# crown-F.net
KiCad netlist of a schematic drawn in EAGLE
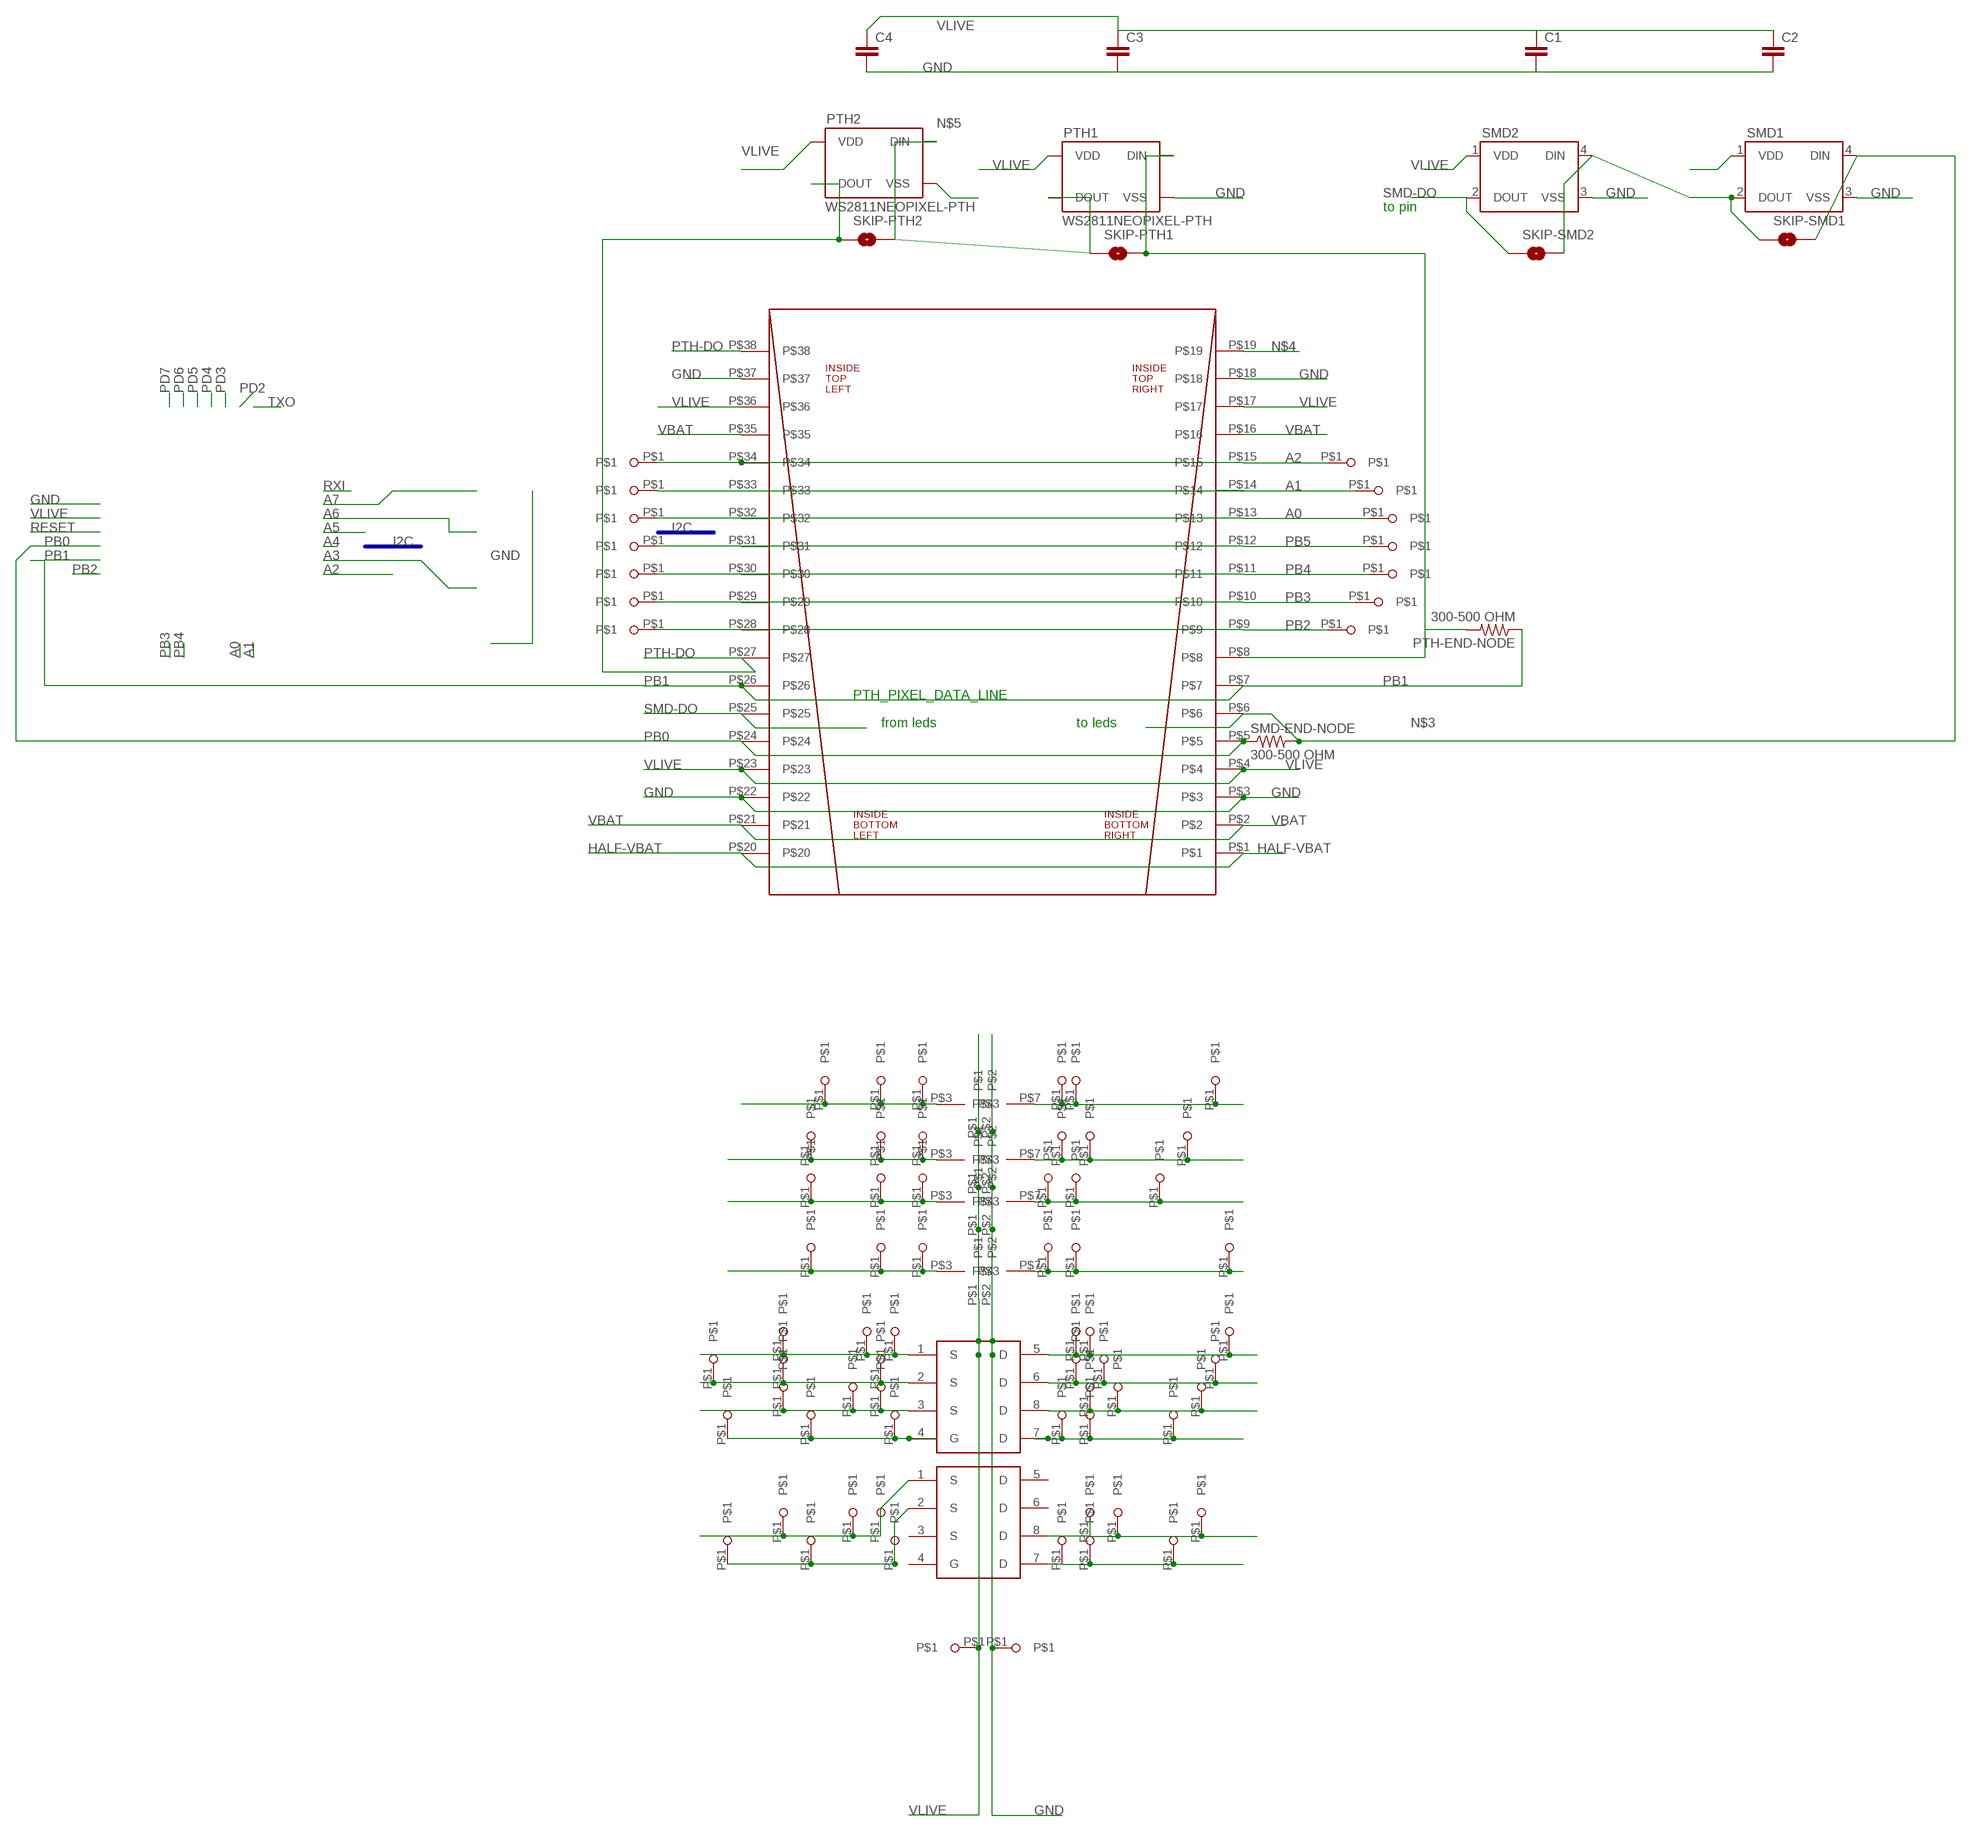
[diagram p0: schematic, sheet 1]

(export (version "E")
  (design (tool "Eeschema 10.0.6"))
  (components
    (comp (ref "C1")
      (value "CAP0805")
      (footprint "eagle-import:0805")
      (libsource (lib "eagle-import") (part "CAP0805"))
    )
    (comp (ref "C2")
      (value "CAP0805")
      (footprint "eagle-import:0805")
      (libsource (lib "eagle-import") (part "CAP0805"))
    )
    (comp (ref "C3")
      (value "CAP0805")
      (footprint "eagle-import:0805")
      (libsource (lib "eagle-import") (part "CAP0805"))
    )
    (comp (ref "C4")
      (value "CAP0805")
      (footprint "eagle-import:0805")
      (libsource (lib "eagle-import") (part "CAP0805"))
    )
    (comp (ref "PTH-END-NODE")
      (value "300-500 OHM")
      (footprint "eagle-import:0805")
      (libsource (lib "eagle-import") (part "RESISTOR0805-RES"))
    )
    (comp (ref "PTH1")
      (value "WS2811NEOPIXEL-PTH")
      (footprint "eagle-import:WS2811-PTH-FLAT")
      (libsource (lib "eagle-import") (part "WS2811NEOPIXEL-PTH"))
    )
    (comp (ref "PTH2")
      (value "WS2811NEOPIXEL-PTH")
      (footprint "eagle-import:WS2811-PTH-FLAT")
      (libsource (lib "eagle-import") (part "WS2811NEOPIXEL-PTH"))
    )
    (comp (ref "SKIP-PTH1")
      (value "SOLDERJUMPERNC2")
      (footprint "eagle-import:SJ_2S-NOTRACE")
      (libsource (lib "eagle-import") (part "SOLDERJUMPERNC2"))
    )
    (comp (ref "SKIP-PTH2")
      (value "SOLDERJUMPERNC2")
      (footprint "eagle-import:SJ_2S-NOTRACE")
      (libsource (lib "eagle-import") (part "SOLDERJUMPERNC2"))
    )
    (comp (ref "SKIP-SMD1")
      (value "SOLDERJUMPERNC2")
      (footprint "eagle-import:SJ_2S-NOTRACE")
      (libsource (lib "eagle-import") (part "SOLDERJUMPERNC2"))
    )
    (comp (ref "SKIP-SMD2")
      (value "SOLDERJUMPERNC2")
      (footprint "eagle-import:SJ_2S-NOTRACE")
      (libsource (lib "eagle-import") (part "SOLDERJUMPERNC2"))
    )
    (comp (ref "SMD-END-NODE")
      (value "300-500 OHM")
      (footprint "eagle-import:0805")
      (libsource (lib "eagle-import") (part "RESISTOR0805-RES"))
    )
    (comp (ref "SMD1")
      (value "WS2812B")
      (footprint "eagle-import:WS2812B")
      (libsource (lib "eagle-import") (part "WS2812B"))
    )
    (comp (ref "SMD2")
      (value "WS2812B")
      (footprint "eagle-import:WS2812B")
      (libsource (lib "eagle-import") (part "WS2812B"))
    )
    (comp (ref "U$1")
      (value "SMD_PAD")
      (footprint "eagle-import:SMD_BREADBOARD_PAD")
      (libsource (lib "eagle-import") (part "SMD_PAD"))
    )
    (comp (ref "U$2")
      (value "CROWNSTANDARD")
      (footprint "eagle-import:CROWN")
      (libsource (lib "eagle-import") (part "CROWNSTANDARD"))
    )
    (comp (ref "U$3")
      (value "SMD_PAD")
      (footprint "eagle-import:SMD_BREADBOARD_PAD")
      (libsource (lib "eagle-import") (part "SMD_PAD"))
    )
    (comp (ref "U$4")
      (value "SMD_BREADBOARD")
      (footprint "eagle-import:SMD_BREADBOARD_4X")
      (libsource (lib "eagle-import") (part "SMD_BREADBOARD"))
    )
    (comp (ref "U$5")
      (value "SMD_BREADBOARD")
      (footprint "eagle-import:SMD_BREADBOARD_4X")
      (libsource (lib "eagle-import") (part "SMD_BREADBOARD"))
    )
    (comp (ref "U$6")
      (value "SMD_BREADBOARD")
      (footprint "eagle-import:SMD_BREADBOARD_4X")
      (libsource (lib "eagle-import") (part "SMD_BREADBOARD"))
    )
    (comp (ref "U$7")
      (value "SMD_BREADBOARD")
      (footprint "eagle-import:SMD_BREADBOARD_4X")
      (libsource (lib "eagle-import") (part "SMD_BREADBOARD"))
    )
    (comp (ref "U$8")
      (value "SMD_PAD")
      (footprint "eagle-import:SMD_BREADBOARD_PAD")
      (libsource (lib "eagle-import") (part "SMD_PAD"))
    )
    (comp (ref "U$9")
      (value "SMD_PAD")
      (footprint "eagle-import:SMD_BREADBOARD_PAD")
      (libsource (lib "eagle-import") (part "SMD_PAD"))
    )
    (comp (ref "U$10")
      (value "SMD_PAD")
      (footprint "eagle-import:SMD_BREADBOARD_PAD")
      (libsource (lib "eagle-import") (part "SMD_PAD"))
    )
    (comp (ref "U$11")
      (value "SMD_PAD")
      (footprint "eagle-import:SMD_BREADBOARD_PAD")
      (libsource (lib "eagle-import") (part "SMD_PAD"))
    )
    (comp (ref "U$12")
      (value "SMD_PAD")
      (footprint "eagle-import:SMD_BREADBOARD_PAD")
      (libsource (lib "eagle-import") (part "SMD_PAD"))
    )
    (comp (ref "U$13")
      (value "SMD_PAD")
      (footprint "eagle-import:SMD_BREADBOARD_PAD")
      (libsource (lib "eagle-import") (part "SMD_PAD"))
    )
    (comp (ref "U$14")
      (value "SMD_PAD")
      (footprint "eagle-import:SMD_BREADBOARD_PAD")
      (libsource (lib "eagle-import") (part "SMD_PAD"))
    )
    (comp (ref "U$15")
      (value "SMD_PAD")
      (footprint "eagle-import:SMD_BREADBOARD_PAD")
      (libsource (lib "eagle-import") (part "SMD_PAD"))
    )
    (comp (ref "U$16")
      (value "SMD_PAD")
      (footprint "eagle-import:SMD_BREADBOARD_PAD")
      (libsource (lib "eagle-import") (part "SMD_PAD"))
    )
    (comp (ref "U$17")
      (value "SMD_PAD")
      (footprint "eagle-import:SMD_BREADBOARD_PAD")
      (libsource (lib "eagle-import") (part "SMD_PAD"))
    )
    (comp (ref "U$18")
      (value "SMD_PAD")
      (footprint "eagle-import:SMD_BREADBOARD_PAD")
      (libsource (lib "eagle-import") (part "SMD_PAD"))
    )
    (comp (ref "U$19")
      (value "SMD_PAD")
      (footprint "eagle-import:SMD_BREADBOARD_PAD")
      (libsource (lib "eagle-import") (part "SMD_PAD"))
    )
    (comp (ref "U$20")
      (value "SMD_PAD")
      (footprint "eagle-import:SMD_BREADBOARD_PAD")
      (libsource (lib "eagle-import") (part "SMD_PAD"))
    )
    (comp (ref "U$21")
      (value "SMD_PAD")
      (footprint "eagle-import:SMD_BREADBOARD_PAD")
      (libsource (lib "eagle-import") (part "SMD_PAD"))
    )
    (comp (ref "U$22")
      (value "SMD_PAD")
      (footprint "eagle-import:SMD_BREADBOARD_PAD")
      (libsource (lib "eagle-import") (part "SMD_PAD"))
    )
    (comp (ref "U$23")
      (value "SMD_PAD")
      (footprint "eagle-import:SMD_BREADBOARD_PAD")
      (libsource (lib "eagle-import") (part "SMD_PAD"))
    )
    (comp (ref "U$24")
      (value "SMD_PAD")
      (footprint "eagle-import:SMD_BREADBOARD_PAD")
      (libsource (lib "eagle-import") (part "SMD_PAD"))
    )
    (comp (ref "U$25")
      (value "SMD_PAD")
      (footprint "eagle-import:SMD_BREADBOARD_PAD")
      (libsource (lib "eagle-import") (part "SMD_PAD"))
    )
    (comp (ref "U$26")
      (value "SMD_PAD")
      (footprint "eagle-import:SMD_BREADBOARD_PAD")
      (libsource (lib "eagle-import") (part "SMD_PAD"))
    )
    (comp (ref "U$27")
      (value "SMD_PAD")
      (footprint "eagle-import:SMD_BREADBOARD_PAD")
      (libsource (lib "eagle-import") (part "SMD_PAD"))
    )
    (comp (ref "U$28")
      (value "SMD_PAD")
      (footprint "eagle-import:SMD_BREADBOARD_PAD")
      (libsource (lib "eagle-import") (part "SMD_PAD"))
    )
    (comp (ref "U$29")
      (value "SMD_PAD")
      (footprint "eagle-import:SMD_BREADBOARD_PAD")
      (libsource (lib "eagle-import") (part "SMD_PAD"))
    )
    (comp (ref "U$30")
      (value "SMD_PAD")
      (footprint "eagle-import:SMD_BREADBOARD_PAD")
      (libsource (lib "eagle-import") (part "SMD_PAD"))
    )
    (comp (ref "U$31")
      (value "SMD_PAD")
      (footprint "eagle-import:SMD_BREADBOARD_PAD")
      (libsource (lib "eagle-import") (part "SMD_PAD"))
    )
    (comp (ref "U$32")
      (value "SMD_PAD")
      (footprint "eagle-import:SMD_BREADBOARD_PAD")
      (libsource (lib "eagle-import") (part "SMD_PAD"))
    )
    (comp (ref "U$33")
      (value "SMD_PAD")
      (footprint "eagle-import:SMD_BREADBOARD_PAD")
      (libsource (lib "eagle-import") (part "SMD_PAD"))
    )
    (comp (ref "U$34")
      (value "SMD_PAD")
      (footprint "eagle-import:SMD_BREADBOARD_PAD")
      (libsource (lib "eagle-import") (part "SMD_PAD"))
    )
    (comp (ref "U$35")
      (value "SMD_PAD")
      (footprint "eagle-import:SMD_BREADBOARD_PAD")
      (libsource (lib "eagle-import") (part "SMD_PAD"))
    )
    (comp (ref "U$36")
      (value "SMD_PAD")
      (footprint "eagle-import:SMD_BREADBOARD_PAD")
      (libsource (lib "eagle-import") (part "SMD_PAD"))
    )
    (comp (ref "U$37")
      (value "SMD_PAD")
      (footprint "eagle-import:SMD_BREADBOARD_PAD")
      (libsource (lib "eagle-import") (part "SMD_PAD"))
    )
    (comp (ref "U$38")
      (value "SMD_PAD")
      (footprint "eagle-import:SMD_BREADBOARD_PAD")
      (libsource (lib "eagle-import") (part "SMD_PAD"))
    )
    (comp (ref "U$39")
      (value "SMD_PAD")
      (footprint "eagle-import:SMD_BREADBOARD_PAD")
      (libsource (lib "eagle-import") (part "SMD_PAD"))
    )
    (comp (ref "U$40")
      (value "SMD_PAD")
      (footprint "eagle-import:SMD_BREADBOARD_PAD")
      (libsource (lib "eagle-import") (part "SMD_PAD"))
    )
    (comp (ref "U$41")
      (value "SMD_PAD")
      (footprint "eagle-import:SMD_BREADBOARD_PAD")
      (libsource (lib "eagle-import") (part "SMD_PAD"))
    )
    (comp (ref "U$42")
      (value "SMD_PAD")
      (footprint "eagle-import:SMD_BREADBOARD_PAD")
      (libsource (lib "eagle-import") (part "SMD_PAD"))
    )
    (comp (ref "U$43")
      (value "SMD_PAD")
      (footprint "eagle-import:SMD_BREADBOARD_PAD")
      (libsource (lib "eagle-import") (part "SMD_PAD"))
    )
    (comp (ref "U$44")
      (value "SMD_PAD")
      (footprint "eagle-import:SMD_BREADBOARD_PAD")
      (libsource (lib "eagle-import") (part "SMD_PAD"))
    )
    (comp (ref "U$45")
      (value "SMD_PAD")
      (footprint "eagle-import:SMD_BREADBOARD_PAD")
      (libsource (lib "eagle-import") (part "SMD_PAD"))
    )
    (comp (ref "U$46")
      (value "SMD_PAD")
      (footprint "eagle-import:SMD_BREADBOARD_PAD")
      (libsource (lib "eagle-import") (part "SMD_PAD"))
    )
    (comp (ref "U$47")
      (value "SMD_PAD")
      (footprint "eagle-import:SMD_BREADBOARD_PAD")
      (libsource (lib "eagle-import") (part "SMD_PAD"))
    )
    (comp (ref "U$48")
      (value "SMD_PAD")
      (footprint "eagle-import:SMD_BREADBOARD_PAD")
      (libsource (lib "eagle-import") (part "SMD_PAD"))
    )
    (comp (ref "U$49")
      (value "SMD_PAD")
      (footprint "eagle-import:SMD_BREADBOARD_PAD")
      (libsource (lib "eagle-import") (part "SMD_PAD"))
    )
    (comp (ref "U$50")
      (value "SMD_PAD")
      (footprint "eagle-import:SMD_BREADBOARD_PAD")
      (libsource (lib "eagle-import") (part "SMD_PAD"))
    )
    (comp (ref "U$51")
      (value "SMD_PAD")
      (footprint "eagle-import:SMD_BREADBOARD_PAD")
      (libsource (lib "eagle-import") (part "SMD_PAD"))
    )
    (comp (ref "U$52")
      (value "SMD_PAD")
      (footprint "eagle-import:SMD_BREADBOARD_PAD")
      (libsource (lib "eagle-import") (part "SMD_PAD"))
    )
    (comp (ref "U$53")
      (value "SMD_PAD")
      (footprint "eagle-import:SMD_BREADBOARD_PAD")
      (libsource (lib "eagle-import") (part "SMD_PAD"))
    )
    (comp (ref "U$54")
      (value "SMD_PAD")
      (footprint "eagle-import:SMD_BREADBOARD_PAD")
      (libsource (lib "eagle-import") (part "SMD_PAD"))
    )
    (comp (ref "U$55")
      (value "SMD_PAD")
      (footprint "eagle-import:SMD_BREADBOARD_PAD")
      (libsource (lib "eagle-import") (part "SMD_PAD"))
    )
    (comp (ref "U$56")
      (value "SMD_PAD")
      (footprint "eagle-import:SMD_BREADBOARD_PAD")
      (libsource (lib "eagle-import") (part "SMD_PAD"))
    )
    (comp (ref "U$57")
      (value "SMD_PAD")
      (footprint "eagle-import:SMD_BREADBOARD_PAD")
      (libsource (lib "eagle-import") (part "SMD_PAD"))
    )
    (comp (ref "U$58")
      (value "SMD_PAD")
      (footprint "eagle-import:SMD_BREADBOARD_PAD")
      (libsource (lib "eagle-import") (part "SMD_PAD"))
    )
    (comp (ref "U$59")
      (value "SMD_PAD")
      (footprint "eagle-import:SMD_BREADBOARD_PAD")
      (libsource (lib "eagle-import") (part "SMD_PAD"))
    )
    (comp (ref "U$60")
      (value "SMD_PAD")
      (footprint "eagle-import:SMD_BREADBOARD_PAD")
      (libsource (lib "eagle-import") (part "SMD_PAD"))
    )
    (comp (ref "U$61")
      (value "SMD_PAD")
      (footprint "eagle-import:SMD_BREADBOARD_PAD")
      (libsource (lib "eagle-import") (part "SMD_PAD"))
    )
    (comp (ref "U$62")
      (value "SMD_PAD")
      (footprint "eagle-import:SMD_BREADBOARD_PAD")
      (libsource (lib "eagle-import") (part "SMD_PAD"))
    )
    (comp (ref "U$63")
      (value "SMD_PAD")
      (footprint "eagle-import:SMD_BREADBOARD_PAD")
      (libsource (lib "eagle-import") (part "SMD_PAD"))
    )
    (comp (ref "U$64")
      (value "SMD_PAD")
      (footprint "eagle-import:SMD_BREADBOARD_PAD")
      (libsource (lib "eagle-import") (part "SMD_PAD"))
    )
    (comp (ref "U$65")
      (value "SMD_PAD")
      (footprint "eagle-import:SMD_BREADBOARD_PAD")
      (libsource (lib "eagle-import") (part "SMD_PAD"))
    )
    (comp (ref "U$66")
      (value "SMD_PAD")
      (footprint "eagle-import:SMD_BREADBOARD_PAD")
      (libsource (lib "eagle-import") (part "SMD_PAD"))
    )
    (comp (ref "U$67")
      (value "SMD_PAD")
      (footprint "eagle-import:SMD_BREADBOARD_PAD")
      (libsource (lib "eagle-import") (part "SMD_PAD"))
    )
    (comp (ref "U$68")
      (value "SMD_PAD")
      (footprint "eagle-import:SMD_BREADBOARD_PAD")
      (libsource (lib "eagle-import") (part "SMD_PAD"))
    )
    (comp (ref "U$69")
      (value "SMD_PAD")
      (footprint "eagle-import:SMD_BREADBOARD_PAD")
      (libsource (lib "eagle-import") (part "SMD_PAD"))
    )
    (comp (ref "U$70")
      (value "SMD_PAD")
      (footprint "eagle-import:SMD_BREADBOARD_PAD")
      (libsource (lib "eagle-import") (part "SMD_PAD"))
    )
    (comp (ref "U$71")
      (value "SMD_PAD")
      (footprint "eagle-import:SMD_BREADBOARD_PAD")
      (libsource (lib "eagle-import") (part "SMD_PAD"))
    )
    (comp (ref "U$72")
      (value "NDS8434")
      (footprint "eagle-import:SO08")
      (libsource (lib "eagle-import") (part "NDS8434"))
    )
    (comp (ref "U$73")
      (value "SMD_PAD")
      (footprint "eagle-import:SMD_BREADBOARD_PAD")
      (libsource (lib "eagle-import") (part "SMD_PAD"))
    )
    (comp (ref "U$74")
      (value "SMD_PAD")
      (footprint "eagle-import:SMD_BREADBOARD_PAD")
      (libsource (lib "eagle-import") (part "SMD_PAD"))
    )
    (comp (ref "U$75")
      (value "SMD_PAD")
      (footprint "eagle-import:SMD_BREADBOARD_PAD")
      (libsource (lib "eagle-import") (part "SMD_PAD"))
    )
    (comp (ref "U$76")
      (value "SMD_PAD")
      (footprint "eagle-import:SMD_BREADBOARD_PAD")
      (libsource (lib "eagle-import") (part "SMD_PAD"))
    )
    (comp (ref "U$77")
      (value "SMD_PAD")
      (footprint "eagle-import:SMD_BREADBOARD_PAD")
      (libsource (lib "eagle-import") (part "SMD_PAD"))
    )
    (comp (ref "U$78")
      (value "SMD_PAD")
      (footprint "eagle-import:SMD_BREADBOARD_PAD")
      (libsource (lib "eagle-import") (part "SMD_PAD"))
    )
    (comp (ref "U$79")
      (value "SMD_PAD")
      (footprint "eagle-import:SMD_BREADBOARD_PAD")
      (libsource (lib "eagle-import") (part "SMD_PAD"))
    )
    (comp (ref "U$80")
      (value "SMD_PAD")
      (footprint "eagle-import:SMD_BREADBOARD_PAD")
      (libsource (lib "eagle-import") (part "SMD_PAD"))
    )
    (comp (ref "U$81")
      (value "NDS8434")
      (footprint "eagle-import:SO08")
      (libsource (lib "eagle-import") (part "NDS8434"))
    )
    (comp (ref "U$82")
      (value "SMD_PAD")
      (footprint "eagle-import:SMD_BREADBOARD_PAD")
      (libsource (lib "eagle-import") (part "SMD_PAD"))
    )
    (comp (ref "U$83")
      (value "SMD_PAD")
      (footprint "eagle-import:SMD_BREADBOARD_PAD")
      (libsource (lib "eagle-import") (part "SMD_PAD"))
    )
  )
  (nets
    (net (code "2") (name "/A0") (class "Default")
      (node (ref "U$2") (pin "P$13") (pinfunction "P$13_P$13") (pintype "bidirectional"))
      (node (ref "U$2") (pin "P$32") (pinfunction "P$32_P$32") (pintype "bidirectional"))
      (node (ref "U$44") (pin "P$1") (pinfunction "P$1_P$1") (pintype "bidirectional"))
      (node (ref "U$55") (pin "P$1") (pinfunction "P$1_P$1") (pintype "bidirectional"))
    )
    (net (code "3") (name "/A1") (class "Default")
      (node (ref "U$2") (pin "P$14") (pinfunction "P$14_P$14") (pintype "bidirectional"))
      (node (ref "U$2") (pin "P$33") (pinfunction "P$33_P$33") (pintype "bidirectional"))
      (node (ref "U$43") (pin "P$1") (pinfunction "P$1_P$1") (pintype "bidirectional"))
      (node (ref "U$56") (pin "P$1") (pinfunction "P$1_P$1") (pintype "bidirectional"))
    )
    (net (code "4") (name "/A2") (class "Default")
      (node (ref "U$2") (pin "P$15") (pinfunction "P$15_P$15") (pintype "bidirectional"))
      (node (ref "U$2") (pin "P$34") (pinfunction "P$34_P$34") (pintype "bidirectional"))
      (node (ref "U$42") (pin "P$1") (pinfunction "P$1_P$1") (pintype "bidirectional"))
      (node (ref "U$58") (pin "P$1") (pinfunction "P$1_P$1") (pintype "bidirectional"))
    )
    (net (code "10") (name "/GND") (class "Default")
      (node (ref "C1") (pin "2") (pinfunction "2_2") (pintype "passive"))
      (node (ref "C2") (pin "2") (pinfunction "2_2") (pintype "passive"))
      (node (ref "C3") (pin "2") (pinfunction "2_2") (pintype "passive"))
      (node (ref "C4") (pin "2") (pinfunction "2_2") (pintype "passive"))
      (node (ref "PTH1") (pin "P$2") (pinfunction "VSS_P$2") (pintype "power_in"))
      (node (ref "PTH1") (pin "P$6") (pinfunction "VSS_P$6") (pintype "power_in"))
      (node (ref "PTH2") (pin "P$2") (pinfunction "VSS_P$2") (pintype "power_in"))
      (node (ref "PTH2") (pin "P$6") (pinfunction "VSS_P$6") (pintype "power_in"))
      (node (ref "SMD1") (pin "3") (pinfunction "VSS_3") (pintype "power_in"))
      (node (ref "SMD2") (pin "3") (pinfunction "VSS_3") (pintype "power_in"))
      (node (ref "U$2") (pin "P$18") (pinfunction "P$18_P$18") (pintype "bidirectional"))
      (node (ref "U$2") (pin "P$22") (pinfunction "P$22_P$22") (pintype "bidirectional"))
      (node (ref "U$2") (pin "P$3") (pinfunction "P$3_P$3") (pintype "bidirectional"))
      (node (ref "U$2") (pin "P$37") (pinfunction "P$37_P$37") (pintype "bidirectional"))
      (node (ref "U$4") (pin "P$2") (pinfunction "P$2_P$2") (pintype "bidirectional"))
      (node (ref "U$5") (pin "P$2") (pinfunction "P$2_P$2") (pintype "bidirectional"))
      (node (ref "U$6") (pin "P$2") (pinfunction "P$2_P$2") (pintype "bidirectional"))
      (node (ref "U$7") (pin "P$2") (pinfunction "P$2_P$2") (pintype "bidirectional"))
      (node (ref "U$83") (pin "P$1") (pinfunction "P$1_P$1") (pintype "bidirectional"))
    )
    (net (code "11") (name "/HALF-VBAT") (class "Default")
      (node (ref "U$2") (pin "P$1") (pinfunction "P$1_P$1") (pintype "bidirectional"))
      (node (ref "U$2") (pin "P$20") (pinfunction "P$20_P$20") (pintype "bidirectional"))
    )
    (net (code "12") (name "/N$3") (class "Default")
      (node (ref "SKIP-SMD1") (pin "2") (pinfunction "2_2") (pintype "passive"))
      (node (ref "SMD-END-NODE") (pin "2") (pinfunction "2_2") (pintype "passive"))
      (node (ref "SMD1") (pin "4") (pinfunction "DIN_4") (pintype "input"))
      (node (ref "U$2") (pin "P$6") (pinfunction "P$6_P$6") (pintype "bidirectional"))
    )
    (net (code "13") (name "/N$4") (class "Default")
      (node (ref "PTH-END-NODE") (pin "2") (pinfunction "2_2") (pintype "passive"))
      (node (ref "PTH1") (pin "P$4") (pinfunction "DIN_P$4") (pintype "input"))
      (node (ref "PTH1") (pin "P$8") (pinfunction "DIN_P$8") (pintype "input"))
      (node (ref "SKIP-PTH1") (pin "2") (pinfunction "2_2") (pintype "passive"))
      (node (ref "U$2") (pin "P$19") (pinfunction "P$19_P$19") (pintype "bidirectional"))
      (node (ref "U$2") (pin "P$8") (pinfunction "P$8_P$8") (pintype "bidirectional"))
    )
    (net (code "14") (name "/N$5") (class "Default")
      (node (ref "PTH1") (pin "P$1") (pinfunction "DOUT_P$1") (pintype "output"))
      (node (ref "PTH1") (pin "P$5") (pinfunction "DOUT_P$5") (pintype "output"))
      (node (ref "PTH2") (pin "P$4") (pinfunction "DIN_P$4") (pintype "input"))
      (node (ref "PTH2") (pin "P$8") (pinfunction "DIN_P$8") (pintype "input"))
      (node (ref "SKIP-PTH1") (pin "1") (pinfunction "1_1") (pintype "passive"))
      (node (ref "SKIP-PTH2") (pin "2") (pinfunction "2_2") (pintype "passive"))
    )
    (net (code "15") (name "/PB0") (class "Default")
      (node (ref "SMD-END-NODE") (pin "1") (pinfunction "1_1") (pintype "passive"))
      (node (ref "U$2") (pin "P$24") (pinfunction "P$24_P$24") (pintype "bidirectional"))
      (node (ref "U$2") (pin "P$5") (pinfunction "P$5_P$5") (pintype "bidirectional"))
    )
    (net (code "16") (name "/PB1") (class "Default")
      (node (ref "PTH-END-NODE") (pin "1") (pinfunction "1_1") (pintype "passive"))
      (node (ref "U$2") (pin "P$26") (pinfunction "P$26_P$26") (pintype "bidirectional"))
      (node (ref "U$2") (pin "P$7") (pinfunction "P$7_P$7") (pintype "bidirectional"))
    )
    (net (code "17") (name "/PB2") (class "Default")
      (node (ref "U$2") (pin "P$28") (pinfunction "P$28_P$28") (pintype "bidirectional"))
      (node (ref "U$2") (pin "P$9") (pinfunction "P$9_P$9") (pintype "bidirectional"))
      (node (ref "U$48") (pin "P$1") (pinfunction "P$1_P$1") (pintype "bidirectional"))
      (node (ref "U$51") (pin "P$1") (pinfunction "P$1_P$1") (pintype "bidirectional"))
    )
    (net (code "18") (name "/PB3") (class "Default")
      (node (ref "U$2") (pin "P$10") (pinfunction "P$10_P$10") (pintype "bidirectional"))
      (node (ref "U$2") (pin "P$29") (pinfunction "P$29_P$29") (pintype "bidirectional"))
      (node (ref "U$47") (pin "P$1") (pinfunction "P$1_P$1") (pintype "bidirectional"))
      (node (ref "U$52") (pin "P$1") (pinfunction "P$1_P$1") (pintype "bidirectional"))
    )
    (net (code "19") (name "/PB4") (class "Default")
      (node (ref "U$2") (pin "P$11") (pinfunction "P$11_P$11") (pintype "bidirectional"))
      (node (ref "U$2") (pin "P$30") (pinfunction "P$30_P$30") (pintype "bidirectional"))
      (node (ref "U$46") (pin "P$1") (pinfunction "P$1_P$1") (pintype "bidirectional"))
      (node (ref "U$53") (pin "P$1") (pinfunction "P$1_P$1") (pintype "bidirectional"))
    )
    (net (code "20") (name "/PB5") (class "Default")
      (node (ref "U$2") (pin "P$12") (pinfunction "P$12_P$12") (pintype "bidirectional"))
      (node (ref "U$2") (pin "P$31") (pinfunction "P$31_P$31") (pintype "bidirectional"))
      (node (ref "U$45") (pin "P$1") (pinfunction "P$1_P$1") (pintype "bidirectional"))
      (node (ref "U$54") (pin "P$1") (pinfunction "P$1_P$1") (pintype "bidirectional"))
    )
    (net (code "27") (name "/PTH-DO") (class "Default")
      (node (ref "PTH2") (pin "P$1") (pinfunction "DOUT_P$1") (pintype "output"))
      (node (ref "PTH2") (pin "P$5") (pinfunction "DOUT_P$5") (pintype "output"))
      (node (ref "SKIP-PTH2") (pin "1") (pinfunction "1_1") (pintype "passive"))
      (node (ref "U$2") (pin "P$27") (pinfunction "P$27_P$27") (pintype "bidirectional"))
      (node (ref "U$2") (pin "P$38") (pinfunction "P$38_P$38") (pintype "bidirectional"))
    )
    (net (code "30") (name "/SMD-DO") (class "Default")
      (node (ref "SKIP-SMD2") (pin "1") (pinfunction "1_1") (pintype "passive"))
      (node (ref "SMD2") (pin "2") (pinfunction "DOUT_2") (pintype "output"))
      (node (ref "U$2") (pin "P$25") (pinfunction "P$25_P$25") (pintype "bidirectional"))
    )
    (net (code "32") (name "/VBAT") (class "Default")
      (node (ref "U$2") (pin "P$16") (pinfunction "P$16_P$16") (pintype "bidirectional"))
      (node (ref "U$2") (pin "P$2") (pinfunction "P$2_P$2") (pintype "bidirectional"))
      (node (ref "U$2") (pin "P$21") (pinfunction "P$21_P$21") (pintype "bidirectional"))
      (node (ref "U$2") (pin "P$35") (pinfunction "P$35_P$35") (pintype "bidirectional"))
    )
    (net (code "33") (name "/VLIVE") (class "Default")
      (node (ref "C1") (pin "1") (pinfunction "1_1") (pintype "passive"))
      (node (ref "C2") (pin "1") (pinfunction "1_1") (pintype "passive"))
      (node (ref "C3") (pin "1") (pinfunction "1_1") (pintype "passive"))
      (node (ref "C4") (pin "1") (pinfunction "1_1") (pintype "passive"))
      (node (ref "PTH1") (pin "P$3") (pinfunction "VDD_P$3") (pintype "power_in"))
      (node (ref "PTH1") (pin "P$7") (pinfunction "VDD_P$7") (pintype "power_in"))
      (node (ref "PTH2") (pin "P$3") (pinfunction "VDD_P$3") (pintype "power_in"))
      (node (ref "PTH2") (pin "P$7") (pinfunction "VDD_P$7") (pintype "power_in"))
      (node (ref "SMD1") (pin "1") (pinfunction "VDD_1") (pintype "power_in"))
      (node (ref "SMD2") (pin "1") (pinfunction "VDD_1") (pintype "power_in"))
      (node (ref "U$2") (pin "P$17") (pinfunction "P$17_P$17") (pintype "bidirectional"))
      (node (ref "U$2") (pin "P$23") (pinfunction "P$23_P$23") (pintype "bidirectional"))
      (node (ref "U$2") (pin "P$36") (pinfunction "P$36_P$36") (pintype "bidirectional"))
      (node (ref "U$2") (pin "P$4") (pinfunction "P$4_P$4") (pintype "bidirectional"))
      (node (ref "U$4") (pin "P$1") (pinfunction "P$1_P$1") (pintype "bidirectional"))
      (node (ref "U$5") (pin "P$1") (pinfunction "P$1_P$1") (pintype "bidirectional"))
      (node (ref "U$6") (pin "P$1") (pinfunction "P$1_P$1") (pintype "bidirectional"))
      (node (ref "U$7") (pin "P$1") (pinfunction "P$1_P$1") (pintype "bidirectional"))
      (node (ref "U$82") (pin "P$1") (pinfunction "P$1_P$1") (pintype "bidirectional"))
    )
    (net (code "35") (name "Net-(SMD1-DOUT)") (class "Default")
      (node (ref "SKIP-SMD1") (pin "1") (pinfunction "1_1") (pintype "passive"))
      (node (ref "SKIP-SMD2") (pin "2") (pinfunction "2_2") (pintype "passive"))
      (node (ref "SMD1") (pin "2") (pinfunction "DOUT_2") (pintype "output"))
      (node (ref "SMD2") (pin "4") (pinfunction "DIN_4") (pintype "input"))
    )
    (net (code "36") (name "Net-(U$1-PadP$1)") (class "Default")
      (node (ref "U$1") (pin "P$1") (pinfunction "P$1_P$1") (pintype "bidirectional"))
      (node (ref "U$3") (pin "P$1") (pinfunction "P$1_P$1") (pintype "bidirectional"))
      (node (ref "U$77") (pin "P$1") (pinfunction "P$1_P$1") (pintype "bidirectional"))
      (node (ref "U$81") (pin "1") (pinfunction "S_1") (pintype "bidirectional"))
    )
    (net (code "37") (name "Net-(U$4-P$4)") (class "Default")
      (node (ref "U$34") (pin "P$1") (pinfunction "P$1_P$1") (pintype "bidirectional"))
      (node (ref "U$35") (pin "P$1") (pinfunction "P$1_P$1") (pintype "bidirectional"))
      (node (ref "U$4") (pin "P$7") (pinfunction "P$4_P$7") (pintype "bidirectional"))
      (node (ref "U$68") (pin "P$1") (pinfunction "P$1_P$1") (pintype "bidirectional"))
    )
    (net (code "38") (name "Net-(U$5-P$4)") (class "Default")
      (node (ref "U$36") (pin "P$1") (pinfunction "P$1_P$1") (pintype "bidirectional"))
      (node (ref "U$37") (pin "P$1") (pinfunction "P$1_P$1") (pintype "bidirectional"))
      (node (ref "U$5") (pin "P$7") (pinfunction "P$4_P$7") (pintype "bidirectional"))
      (node (ref "U$69") (pin "P$1") (pinfunction "P$1_P$1") (pintype "bidirectional"))
    )
    (net (code "39") (name "Net-(U$6-P$4)") (class "Default")
      (node (ref "U$38") (pin "P$1") (pinfunction "P$1_P$1") (pintype "bidirectional"))
      (node (ref "U$39") (pin "P$1") (pinfunction "P$1_P$1") (pintype "bidirectional"))
      (node (ref "U$6") (pin "P$7") (pinfunction "P$4_P$7") (pintype "bidirectional"))
      (node (ref "U$70") (pin "P$1") (pinfunction "P$1_P$1") (pintype "bidirectional"))
    )
    (net (code "40") (name "Net-(U$7-P$4)") (class "Default")
      (node (ref "U$40") (pin "P$1") (pinfunction "P$1_P$1") (pintype "bidirectional"))
      (node (ref "U$41") (pin "P$1") (pinfunction "P$1_P$1") (pintype "bidirectional"))
      (node (ref "U$7") (pin "P$7") (pinfunction "P$4_P$7") (pintype "bidirectional"))
      (node (ref "U$71") (pin "P$1") (pinfunction "P$1_P$1") (pintype "bidirectional"))
    )
    (net (code "41") (name "Net-(U$10-PadP$1)") (class "Default")
      (node (ref "U$10") (pin "P$1") (pinfunction "P$1_P$1") (pintype "bidirectional"))
      (node (ref "U$11") (pin "P$1") (pinfunction "P$1_P$1") (pintype "bidirectional"))
      (node (ref "U$49") (pin "P$1") (pinfunction "P$1_P$1") (pintype "bidirectional"))
      (node (ref "U$7") (pin "P$3") (pinfunction "P$3_P$3") (pintype "bidirectional"))
    )
    (net (code "42") (name "Net-(U$12-PadP$1)") (class "Default")
      (node (ref "U$12") (pin "P$1") (pinfunction "P$1_P$1") (pintype "bidirectional"))
      (node (ref "U$13") (pin "P$1") (pinfunction "P$1_P$1") (pintype "bidirectional"))
      (node (ref "U$50") (pin "P$1") (pinfunction "P$1_P$1") (pintype "bidirectional"))
      (node (ref "U$6") (pin "P$3") (pinfunction "P$3_P$3") (pintype "bidirectional"))
    )
    (net (code "43") (name "Net-(U$14-PadP$1)") (class "Default")
      (node (ref "U$14") (pin "P$1") (pinfunction "P$1_P$1") (pintype "bidirectional"))
      (node (ref "U$15") (pin "P$1") (pinfunction "P$1_P$1") (pintype "bidirectional"))
      (node (ref "U$5") (pin "P$3") (pinfunction "P$3_P$3") (pintype "bidirectional"))
      (node (ref "U$57") (pin "P$1") (pinfunction "P$1_P$1") (pintype "bidirectional"))
    )
    (net (code "44") (name "Net-(U$16-PadP$1)") (class "Default")
      (node (ref "U$16") (pin "P$1") (pinfunction "P$1_P$1") (pintype "bidirectional"))
      (node (ref "U$17") (pin "P$1") (pinfunction "P$1_P$1") (pintype "bidirectional"))
      (node (ref "U$4") (pin "P$3") (pinfunction "P$3_P$3") (pintype "bidirectional"))
      (node (ref "U$59") (pin "P$1") (pinfunction "P$1_P$1") (pintype "bidirectional"))
    )
    (net (code "45") (name "Net-(U$18-PadP$1)") (class "Default")
      (node (ref "U$18") (pin "P$1") (pinfunction "P$1_P$1") (pintype "bidirectional"))
      (node (ref "U$19") (pin "P$1") (pinfunction "P$1_P$1") (pintype "bidirectional"))
      (node (ref "U$60") (pin "P$1") (pinfunction "P$1_P$1") (pintype "bidirectional"))
      (node (ref "U$72") (pin "1") (pinfunction "S_1") (pintype "bidirectional"))
    )
    (net (code "46") (name "Net-(U$20-PadP$1)") (class "Default")
      (node (ref "U$20") (pin "P$1") (pinfunction "P$1_P$1") (pintype "bidirectional"))
      (node (ref "U$21") (pin "P$1") (pinfunction "P$1_P$1") (pintype "bidirectional"))
      (node (ref "U$61") (pin "P$1") (pinfunction "P$1_P$1") (pintype "bidirectional"))
      (node (ref "U$72") (pin "2") (pinfunction "S_2") (pintype "bidirectional"))
    )
    (net (code "47") (name "Net-(U$22-PadP$1)") (class "Default")
      (node (ref "U$22") (pin "P$1") (pinfunction "P$1_P$1") (pintype "bidirectional"))
      (node (ref "U$23") (pin "P$1") (pinfunction "P$1_P$1") (pintype "bidirectional"))
      (node (ref "U$62") (pin "P$1") (pinfunction "P$1_P$1") (pintype "bidirectional"))
      (node (ref "U$72") (pin "3") (pinfunction "S_3") (pintype "bidirectional"))
    )
    (net (code "48") (name "Net-(U$26-PadP$1)") (class "Default")
      (node (ref "U$26") (pin "P$1") (pinfunction "P$1_P$1") (pintype "bidirectional"))
      (node (ref "U$27") (pin "P$1") (pinfunction "P$1_P$1") (pintype "bidirectional"))
      (node (ref "U$64") (pin "P$1") (pinfunction "P$1_P$1") (pintype "bidirectional"))
      (node (ref "U$72") (pin "7") (pinfunction "D_7") (pintype "bidirectional"))
    )
    (net (code "49") (name "Net-(U$28-PadP$1)") (class "Default")
      (node (ref "U$28") (pin "P$1") (pinfunction "P$1_P$1") (pintype "bidirectional"))
      (node (ref "U$29") (pin "P$1") (pinfunction "P$1_P$1") (pintype "bidirectional"))
      (node (ref "U$65") (pin "P$1") (pinfunction "P$1_P$1") (pintype "bidirectional"))
      (node (ref "U$72") (pin "8") (pinfunction "D_8") (pintype "bidirectional"))
    )
    (net (code "50") (name "Net-(U$30-PadP$1)") (class "Default")
      (node (ref "U$30") (pin "P$1") (pinfunction "P$1_P$1") (pintype "bidirectional"))
      (node (ref "U$31") (pin "P$1") (pinfunction "P$1_P$1") (pintype "bidirectional"))
      (node (ref "U$66") (pin "P$1") (pinfunction "P$1_P$1") (pintype "bidirectional"))
      (node (ref "U$72") (pin "6") (pinfunction "D_6") (pintype "bidirectional"))
    )
    (net (code "51") (name "Net-(U$32-PadP$1)") (class "Default")
      (node (ref "U$32") (pin "P$1") (pinfunction "P$1_P$1") (pintype "bidirectional"))
      (node (ref "U$33") (pin "P$1") (pinfunction "P$1_P$1") (pintype "bidirectional"))
      (node (ref "U$67") (pin "P$1") (pinfunction "P$1_P$1") (pintype "bidirectional"))
      (node (ref "U$72") (pin "5") (pinfunction "D_5") (pintype "bidirectional"))
    )
    (net (code "52") (name "Net-(U$72-G)") (class "Default")
      (node (ref "U$24") (pin "P$1") (pinfunction "P$1_P$1") (pintype "bidirectional"))
      (node (ref "U$25") (pin "P$1") (pinfunction "P$1_P$1") (pintype "bidirectional"))
      (node (ref "U$63") (pin "P$1") (pinfunction "P$1_P$1") (pintype "bidirectional"))
      (node (ref "U$72") (pin "4") (pinfunction "G_4") (pintype "bidirectional"))
    )
    (net (code "53") (name "Net-(U$73-PadP$1)") (class "Default")
      (node (ref "U$73") (pin "P$1") (pinfunction "P$1_P$1") (pintype "bidirectional"))
      (node (ref "U$74") (pin "P$1") (pinfunction "P$1_P$1") (pintype "bidirectional"))
      (node (ref "U$79") (pin "P$1") (pinfunction "P$1_P$1") (pintype "bidirectional"))
      (node (ref "U$81") (pin "7") (pinfunction "D_7") (pintype "bidirectional"))
    )
    (net (code "54") (name "Net-(U$75-PadP$1)") (class "Default")
      (node (ref "U$75") (pin "P$1") (pinfunction "P$1_P$1") (pintype "bidirectional"))
      (node (ref "U$76") (pin "P$1") (pinfunction "P$1_P$1") (pintype "bidirectional"))
      (node (ref "U$80") (pin "P$1") (pinfunction "P$1_P$1") (pintype "bidirectional"))
      (node (ref "U$81") (pin "8") (pinfunction "D_8") (pintype "bidirectional"))
    )
    (net (code "55") (name "Net-(U$78-PadP$1)") (class "Default")
      (node (ref "U$78") (pin "P$1") (pinfunction "P$1_P$1") (pintype "bidirectional"))
      (node (ref "U$8") (pin "P$1") (pinfunction "P$1_P$1") (pintype "bidirectional"))
      (node (ref "U$81") (pin "2") (pinfunction "S_2") (pintype "bidirectional"))
      (node (ref "U$9") (pin "P$1") (pinfunction "P$1_P$1") (pintype "bidirectional"))
    )
    (net (code "56") (name "unconnected-(U$81-D-Pad5)") (class "Default")
      (node (ref "U$81") (pin "5") (pinfunction "D_5") (pintype "bidirectional"))
    )
    (net (code "57") (name "unconnected-(U$81-D-Pad6)") (class "Default")
      (node (ref "U$81") (pin "6") (pinfunction "D_6") (pintype "bidirectional"))
    )
    (net (code "58") (name "unconnected-(U$81-G-Pad4)") (class "Default")
      (node (ref "U$81") (pin "4") (pinfunction "G_4") (pintype "bidirectional"))
    )
    (net (code "59") (name "unconnected-(U$81-S-Pad3)") (class "Default")
      (node (ref "U$81") (pin "3") (pinfunction "S_3") (pintype "bidirectional"))
    )
  )
)
